# PCB_Schematic_Linefollower.net
KiCad netlist of a schematic drawn in EasyEDA
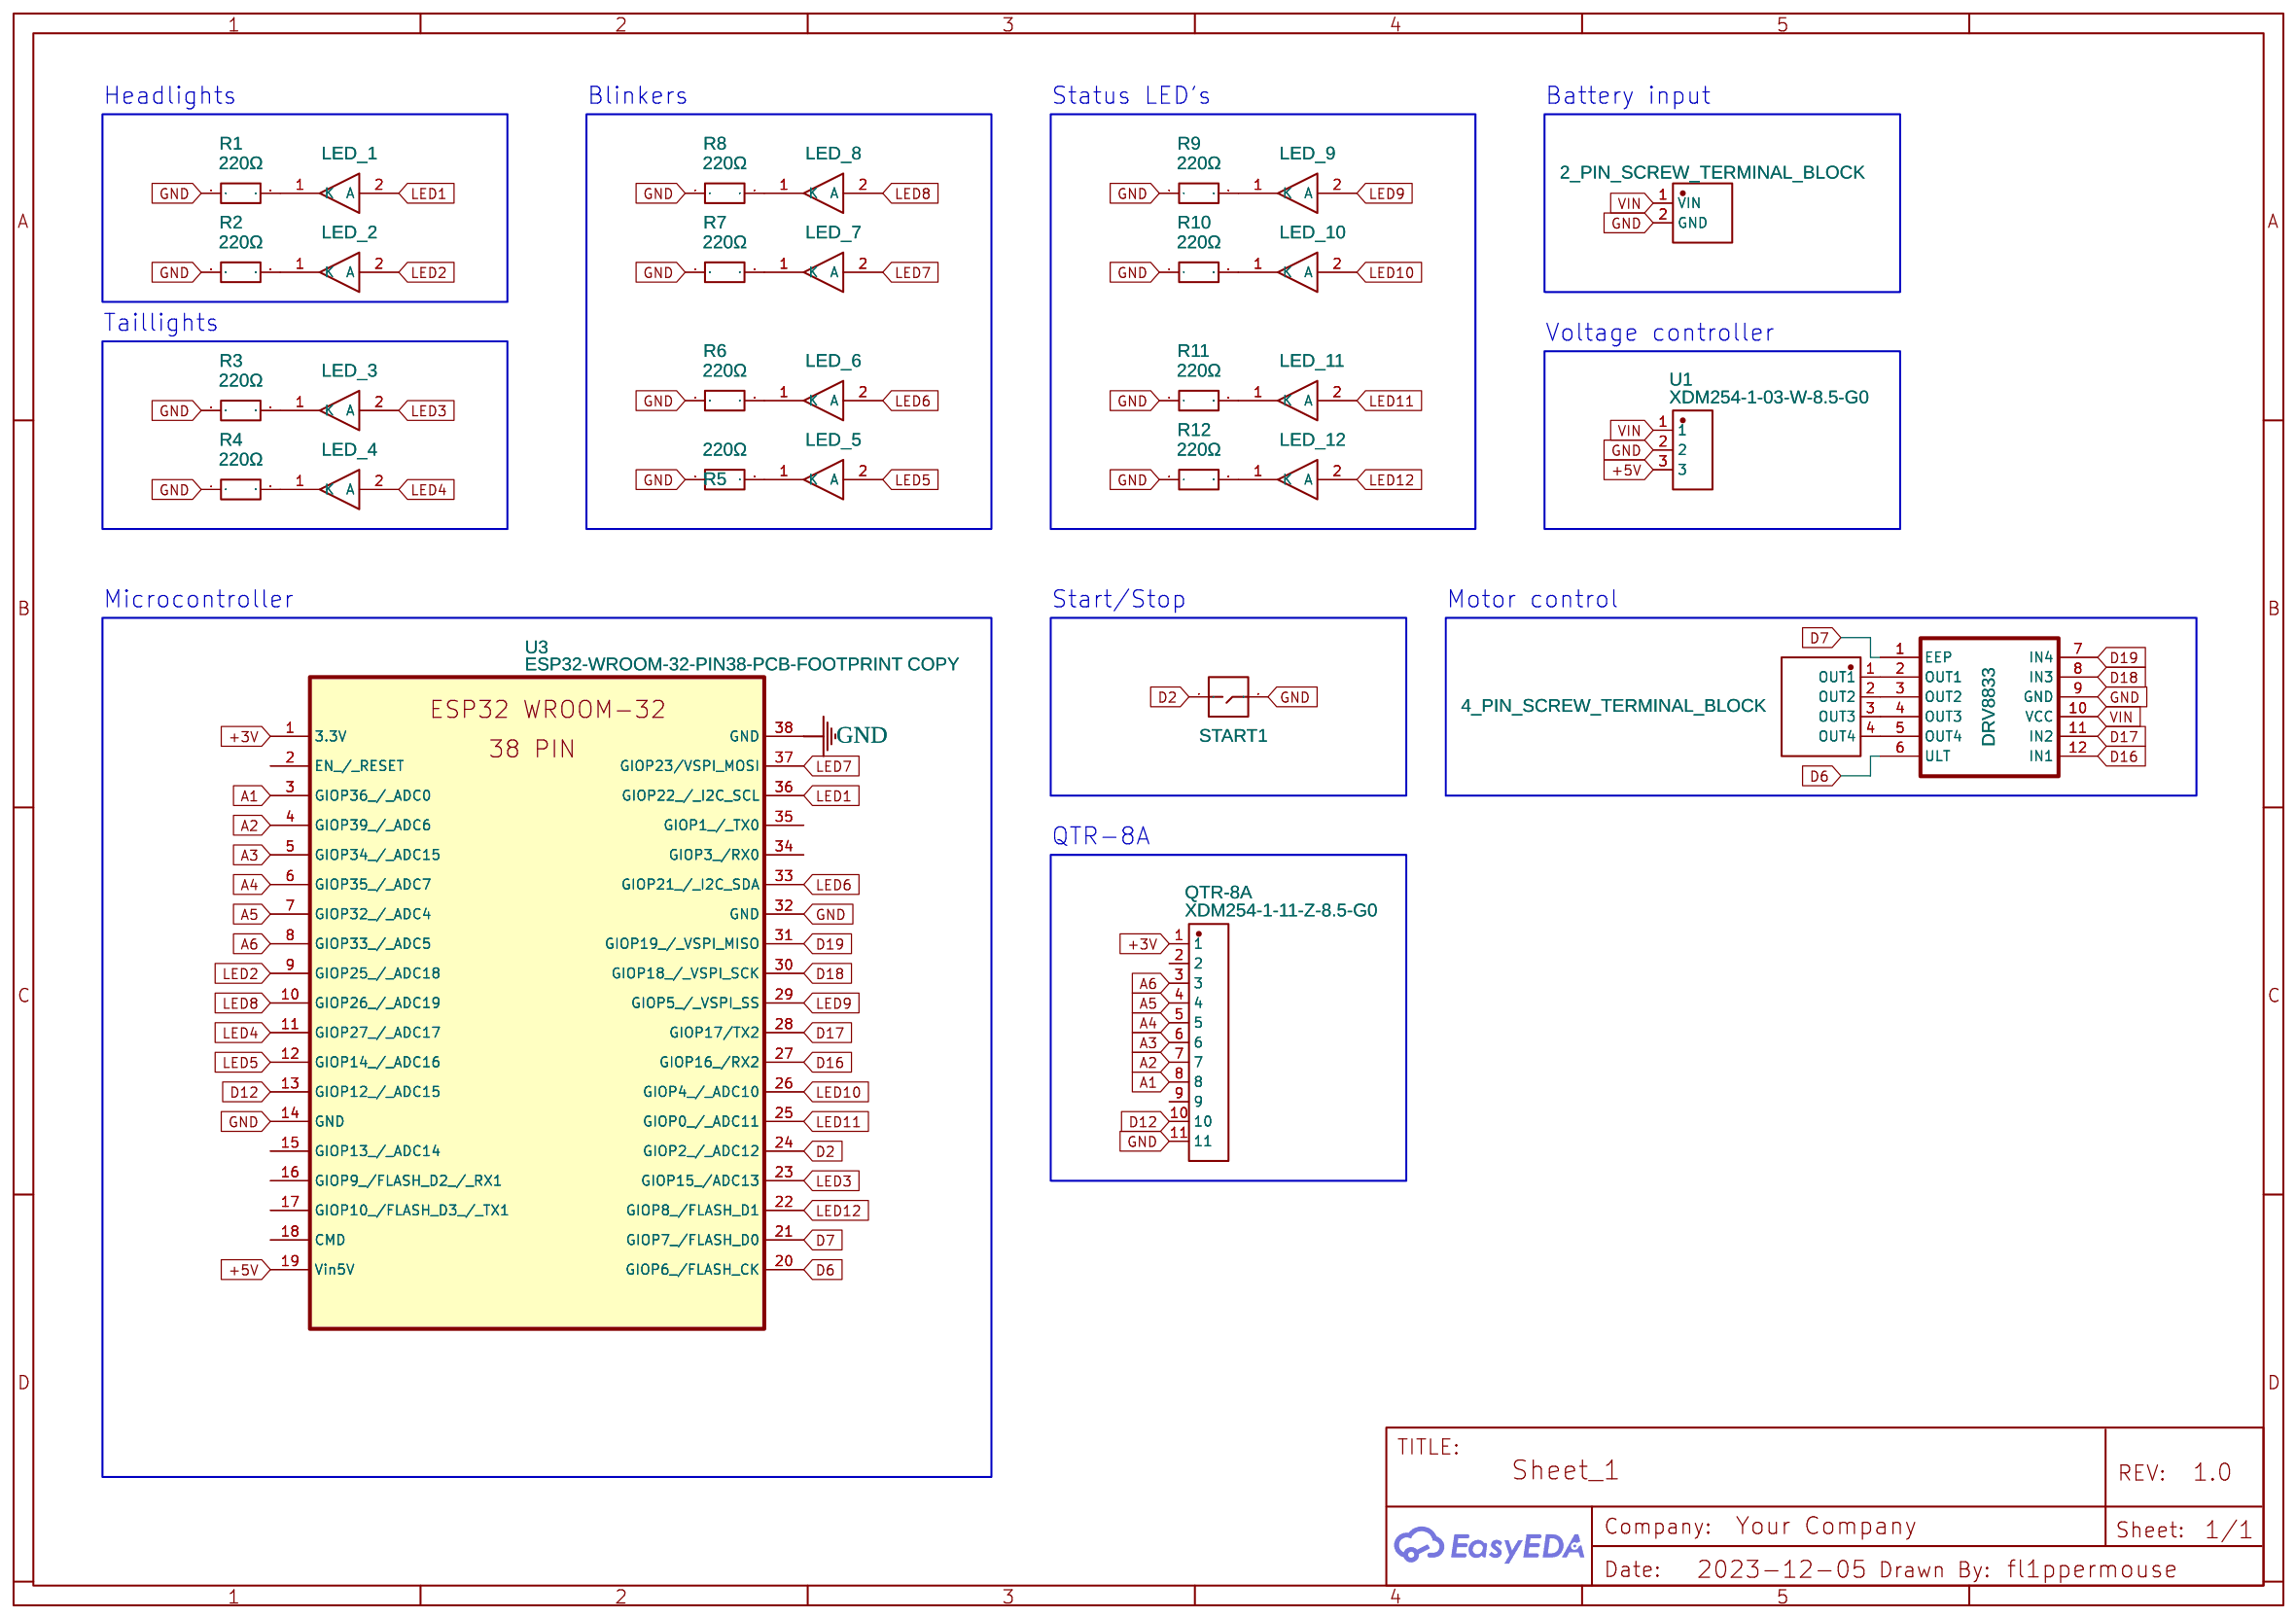
[diagram p0: schematic sheet]

(export (version "E")
  (design (tool "Eeschema 10.0.6"))
  (components
    (comp (ref "2_PIN_SCREW_TERMINAL_BLOCK")
      (value "2 Pin Screw Terminal Block Connector 2.54 mm")
      (libsource (lib "") (part "2 PIN SCREW TERMINAL BLOCK CONNECTOR 2.54 MM"))
    )
    (comp (ref "4_PIN_SCREW_TERMINAL_BLOCK")
      (value "4 PIN SCREW TERMINAL BLOCK CONNECTOR 2.54 MM")
      (libsource (lib "") (part "4 PIN SCREW TERMINAL BLOCK CONNECTOR 2.54 MM"))
    )
    (comp (ref "DRV8833") (value "DRV8833") (libsource (lib "") (part "DRV8833 12PIN")))
    (comp (ref "LED_1") (value "led 5 mm") (libsource (lib "") (part "led 5 mm")))
    (comp (ref "LED_2") (value "led 5 mm") (libsource (lib "") (part "led 5 mm")))
    (comp (ref "LED_3") (value "led 5 mm") (libsource (lib "") (part "led 5 mm")))
    (comp (ref "LED_4") (value "led 5 mm") (libsource (lib "") (part "led 5 mm")))
    (comp (ref "LED_5") (value "led 5 mm") (libsource (lib "") (part "led 5 mm")))
    (comp (ref "LED_6") (value "led 5 mm") (libsource (lib "") (part "led 5 mm")))
    (comp (ref "LED_7") (value "led 5 mm") (libsource (lib "") (part "led 5 mm")))
    (comp (ref "LED_8") (value "led 5 mm") (libsource (lib "") (part "led 5 mm")))
    (comp (ref "LED_9") (value "led 5 mm") (libsource (lib "") (part "led 5 mm")))
    (comp (ref "LED_10") (value "led 5 mm") (libsource (lib "") (part "led 5 mm")))
    (comp (ref "LED_11") (value "led 5 mm") (libsource (lib "") (part "led 5 mm")))
    (comp (ref "LED_12") (value "led 5 mm") (libsource (lib "") (part "led 5 mm")))
    (comp (ref "QTR-8A")
      (value "XDM254-1-11-Z-8.5-G0")
      (fields (field (name "Manufacturer") "XUNDA(讯答)"))
      (libsource (lib "") (part "XDM254-1-11-Z-8.5-G0"))
    )
    (comp (ref "R1")
      (value "220Ω")
      (libsource (lib "") (part "AXIAL RESISTOR 220 OHM - TH_BD2.3-L6.0-P10.00-D0.4"))
    )
    (comp (ref "R2")
      (value "220Ω")
      (libsource (lib "") (part "AXIAL RESISTOR 220 OHM - TH_BD2.3-L6.0-P10.00-D0.4"))
    )
    (comp (ref "R3")
      (value "220Ω")
      (libsource (lib "") (part "AXIAL RESISTOR 220 OHM - TH_BD2.3-L6.0-P10.00-D0.4"))
    )
    (comp (ref "R4")
      (value "220Ω")
      (libsource (lib "") (part "AXIAL RESISTOR 220 OHM - TH_BD2.3-L6.0-P10.00-D0.4"))
    )
    (comp (ref "R5")
      (value "220Ω")
      (libsource (lib "") (part "AXIAL RESISTOR 220 OHM - TH_BD2.3-L6.0-P10.00-D0.4"))
    )
    (comp (ref "R6")
      (value "220Ω")
      (libsource (lib "") (part "AXIAL RESISTOR 220 OHM - TH_BD2.3-L6.0-P10.00-D0.4"))
    )
    (comp (ref "R7")
      (value "220Ω")
      (libsource (lib "") (part "AXIAL RESISTOR 220 OHM - TH_BD2.3-L6.0-P10.00-D0.4"))
    )
    (comp (ref "R8")
      (value "220Ω")
      (libsource (lib "") (part "AXIAL RESISTOR 220 OHM - TH_BD2.3-L6.0-P10.00-D0.4"))
    )
    (comp (ref "R9")
      (value "220Ω")
      (libsource (lib "") (part "AXIAL RESISTOR 220 OHM - TH_BD2.3-L6.0-P10.00-D0.4"))
    )
    (comp (ref "R10")
      (value "220Ω")
      (libsource (lib "") (part "AXIAL RESISTOR 220 OHM - TH_BD2.3-L6.0-P10.00-D0.4"))
    )
    (comp (ref "R11")
      (value "220Ω")
      (libsource (lib "") (part "AXIAL RESISTOR 220 OHM - TH_BD2.3-L6.0-P10.00-D0.4"))
    )
    (comp (ref "R12")
      (value "220Ω")
      (libsource (lib "") (part "AXIAL RESISTOR 220 OHM - TH_BD2.3-L6.0-P10.00-D0.4"))
    )
    (comp (ref "START1") (value "start") (libsource (lib "") (part "Push Button")))
    (comp (ref "U1")
      (value "XDM254-1-03-W-8.5-G0")
      (fields (field (name "Manufacturer") "XUNDA(讯答)"))
      (libsource (lib "") (part "XDM254-1-03-W-8.5-G0"))
    )
    (comp (ref "U3")
      (value "ESP32-WROOM-32-PIN38-PCB-FOOTPRINT COPY")
      (fields
        (field (name "Manufacturer Part") "ESP32-WROOM-32")
        (field (name "Manufacturer") "Espressif Systems")
      )
      (libsource (lib "") (part "ESP32-WROOM-32-PIN38-PCB-FOOTPRINT COPY"))
    )
  )
  (nets
    (net (code "1") (name "+3V") (class "Default")
      (node (ref "QTR-8A") (pin "1") (pinfunction "1_1") (pintype "unspecified"))
      (node (ref "U3") (pin "1") (pinfunction "3.3V_1") (pintype "unspecified"))
    )
    (net (code "2") (name "+5V") (class "Default")
      (node (ref "U1") (pin "3") (pinfunction "3_3") (pintype "unspecified"))
      (node (ref "U3") (pin "19") (pinfunction "Vin5V_19") (pintype "unspecified"))
    )
    (net (code "3") (name "A1") (class "Default")
      (node (ref "QTR-8A") (pin "8") (pinfunction "8_8") (pintype "unspecified"))
      (node (ref "U3") (pin "3") (pinfunction "GIOP36_/_ADC0_3") (pintype "unspecified"))
    )
    (net (code "4") (name "A2") (class "Default")
      (node (ref "QTR-8A") (pin "7") (pinfunction "7_7") (pintype "unspecified"))
      (node (ref "U3") (pin "4") (pinfunction "GIOP39_/_ADC6_4") (pintype "unspecified"))
    )
    (net (code "5") (name "A3") (class "Default")
      (node (ref "QTR-8A") (pin "6") (pinfunction "6_6") (pintype "unspecified"))
      (node (ref "U3") (pin "5") (pinfunction "GIOP34_/_ADC15_5") (pintype "unspecified"))
    )
    (net (code "6") (name "A4") (class "Default")
      (node (ref "QTR-8A") (pin "5") (pinfunction "5_5") (pintype "unspecified"))
      (node (ref "U3") (pin "6") (pinfunction "GIOP35_/_ADC7_6") (pintype "unspecified"))
    )
    (net (code "7") (name "A5") (class "Default")
      (node (ref "QTR-8A") (pin "4") (pinfunction "4_4") (pintype "unspecified"))
      (node (ref "U3") (pin "7") (pinfunction "GIOP32_/_ADC4_7") (pintype "unspecified"))
    )
    (net (code "8") (name "A6") (class "Default")
      (node (ref "QTR-8A") (pin "3") (pinfunction "3_3") (pintype "unspecified"))
      (node (ref "U3") (pin "8") (pinfunction "GIOP33_/_ADC5_8") (pintype "unspecified"))
    )
    (net (code "9") (name "D2") (class "Default")
      (node (ref "START1") (pin "1") (pinfunction "1_1") (pintype "unspecified"))
      (node (ref "U3") (pin "24") (pinfunction "GIOP2_/_ADC12_24") (pintype "unspecified"))
    )
    (net (code "10") (name "D6") (class "Default")
      (node (ref "DRV8833") (pin "6") (pinfunction "ULT_6") (pintype "unspecified"))
      (node (ref "U3") (pin "20") (pinfunction "GIOP6_/FLASH_CK_20") (pintype "unspecified"))
    )
    (net (code "11") (name "D7") (class "Default")
      (node (ref "DRV8833") (pin "1") (pinfunction "EEP_1") (pintype "unspecified"))
      (node (ref "U3") (pin "21") (pinfunction "GIOP7_/FLASH_D0_21") (pintype "unspecified"))
    )
    (net (code "12") (name "D12") (class "Default")
      (node (ref "QTR-8A") (pin "10") (pinfunction "10_10") (pintype "unspecified"))
      (node (ref "U3") (pin "13") (pinfunction "GIOP12_/_ADC15_13") (pintype "unspecified"))
    )
    (net (code "13") (name "D16") (class "Default")
      (node (ref "DRV8833") (pin "12") (pinfunction "IN1_12") (pintype "unspecified"))
      (node (ref "U3") (pin "27") (pinfunction "GIOP16_/RX2_27") (pintype "unspecified"))
    )
    (net (code "14") (name "D17") (class "Default")
      (node (ref "DRV8833") (pin "11") (pinfunction "IN2_11") (pintype "unspecified"))
      (node (ref "U3") (pin "28") (pinfunction "GIOP17/TX2_28") (pintype "unspecified"))
    )
    (net (code "15") (name "D18") (class "Default")
      (node (ref "DRV8833") (pin "8") (pinfunction "IN3_8") (pintype "unspecified"))
      (node (ref "U3") (pin "30") (pinfunction "GIOP18_/_VSPI_SCK_30") (pintype "unspecified"))
    )
    (net (code "16") (name "D19") (class "Default")
      (node (ref "DRV8833") (pin "7") (pinfunction "IN4_7") (pintype "unspecified"))
      (node (ref "U3") (pin "31") (pinfunction "GIOP19_/_VSPI_MISO_31") (pintype "unspecified"))
    )
    (net (code "17") (name "GND") (class "Default")
      (node (ref "2_PIN_SCREW_TERMINAL_BLOCK") (pin "2") (pinfunction "GND_2") (pintype "unspecified"))
      (node (ref "DRV8833") (pin "9") (pinfunction "GND_9") (pintype "unspecified"))
      (node (ref "QTR-8A") (pin "11") (pinfunction "11_11") (pintype "unspecified"))
      (node (ref "R1") (pin "1") (pinfunction "1_1") (pintype "unspecified"))
      (node (ref "R10") (pin "1") (pinfunction "1_1") (pintype "unspecified"))
      (node (ref "R11") (pin "1") (pinfunction "1_1") (pintype "unspecified"))
      (node (ref "R12") (pin "1") (pinfunction "1_1") (pintype "unspecified"))
      (node (ref "R2") (pin "1") (pinfunction "1_1") (pintype "unspecified"))
      (node (ref "R3") (pin "1") (pinfunction "1_1") (pintype "unspecified"))
      (node (ref "R4") (pin "1") (pinfunction "1_1") (pintype "unspecified"))
      (node (ref "R5") (pin "1") (pinfunction "1_1") (pintype "unspecified"))
      (node (ref "R6") (pin "1") (pinfunction "1_1") (pintype "unspecified"))
      (node (ref "R7") (pin "1") (pinfunction "1_1") (pintype "unspecified"))
      (node (ref "R8") (pin "1") (pinfunction "1_1") (pintype "unspecified"))
      (node (ref "R9") (pin "1") (pinfunction "1_1") (pintype "unspecified"))
      (node (ref "START1") (pin "2") (pinfunction "2_2") (pintype "unspecified"))
      (node (ref "U1") (pin "2") (pinfunction "2_2") (pintype "unspecified"))
      (node (ref "U3") (pin "14") (pinfunction "GND_14") (pintype "unspecified"))
      (node (ref "U3") (pin "32") (pinfunction "GND_32") (pintype "unspecified"))
      (node (ref "U3") (pin "38") (pinfunction "GND_38") (pintype "unspecified"))
    )
    (net (code "18") (name "LED1") (class "Default")
      (node (ref "LED_1") (pin "2") (pinfunction "A_2") (pintype "unspecified"))
      (node (ref "U3") (pin "36") (pinfunction "GIOP22_/_I2C_SCL_36") (pintype "unspecified"))
    )
    (net (code "19") (name "LED2") (class "Default")
      (node (ref "LED_2") (pin "2") (pinfunction "A_2") (pintype "unspecified"))
      (node (ref "U3") (pin "9") (pinfunction "GIOP25_/_ADC18_9") (pintype "unspecified"))
    )
    (net (code "20") (name "LED3") (class "Default")
      (node (ref "LED_3") (pin "2") (pinfunction "A_2") (pintype "unspecified"))
      (node (ref "U3") (pin "23") (pinfunction "GIOP15_/ADC13_23") (pintype "unspecified"))
    )
    (net (code "21") (name "LED4") (class "Default")
      (node (ref "LED_4") (pin "2") (pinfunction "A_2") (pintype "unspecified"))
      (node (ref "U3") (pin "11") (pinfunction "GIOP27_/_ADC17_11") (pintype "unspecified"))
    )
    (net (code "22") (name "LED5") (class "Default")
      (node (ref "LED_5") (pin "2") (pinfunction "A_2") (pintype "unspecified"))
      (node (ref "U3") (pin "12") (pinfunction "GIOP14_/_ADC16_12") (pintype "unspecified"))
    )
    (net (code "23") (name "LED6") (class "Default")
      (node (ref "LED_6") (pin "2") (pinfunction "A_2") (pintype "unspecified"))
      (node (ref "U3") (pin "33") (pinfunction "GIOP21_/_I2C_SDA_33") (pintype "unspecified"))
    )
    (net (code "24") (name "LED7") (class "Default")
      (node (ref "LED_7") (pin "2") (pinfunction "A_2") (pintype "unspecified"))
      (node (ref "U3") (pin "37") (pinfunction "GIOP23/VSPI_MOSI_37") (pintype "unspecified"))
    )
    (net (code "25") (name "LED8") (class "Default")
      (node (ref "LED_8") (pin "2") (pinfunction "A_2") (pintype "unspecified"))
      (node (ref "U3") (pin "10") (pinfunction "GIOP26_/_ADC19_10") (pintype "unspecified"))
    )
    (net (code "26") (name "LED9") (class "Default")
      (node (ref "LED_9") (pin "2") (pinfunction "A_2") (pintype "unspecified"))
      (node (ref "U3") (pin "29") (pinfunction "GIOP5_/_VSPI_SS_29") (pintype "unspecified"))
    )
    (net (code "27") (name "LED10") (class "Default")
      (node (ref "LED_10") (pin "2") (pinfunction "A_2") (pintype "unspecified"))
      (node (ref "U3") (pin "26") (pinfunction "GIOP4_/_ADC10_26") (pintype "unspecified"))
    )
    (net (code "28") (name "LED11") (class "Default")
      (node (ref "LED_11") (pin "2") (pinfunction "A_2") (pintype "unspecified"))
      (node (ref "U3") (pin "25") (pinfunction "GIOP0_/_ADC11_25") (pintype "unspecified"))
    )
    (net (code "29") (name "LED12") (class "Default")
      (node (ref "LED_12") (pin "2") (pinfunction "A_2") (pintype "unspecified"))
      (node (ref "U3") (pin "22") (pinfunction "GIOP8_/FLASH_D1_22") (pintype "unspecified"))
    )
    (net (code "30") (name "Net-(4_PIN_SCREW_TERMINAL_BLOCK-OUT1)") (class "Default")
      (node (ref "4_PIN_SCREW_TERMINAL_BLOCK") (pin "1") (pinfunction "OUT1_1") (pintype "unspecified"))
      (node (ref "DRV8833") (pin "2") (pinfunction "OUT1_2") (pintype "unspecified"))
    )
    (net (code "31") (name "Net-(4_PIN_SCREW_TERMINAL_BLOCK-OUT2)") (class "Default")
      (node (ref "4_PIN_SCREW_TERMINAL_BLOCK") (pin "2") (pinfunction "OUT2_2") (pintype "unspecified"))
      (node (ref "DRV8833") (pin "3") (pinfunction "OUT2_3") (pintype "unspecified"))
    )
    (net (code "32") (name "Net-(4_PIN_SCREW_TERMINAL_BLOCK-OUT3)") (class "Default")
      (node (ref "4_PIN_SCREW_TERMINAL_BLOCK") (pin "3") (pinfunction "OUT3_3") (pintype "unspecified"))
      (node (ref "DRV8833") (pin "4") (pinfunction "OUT3_4") (pintype "unspecified"))
    )
    (net (code "33") (name "Net-(4_PIN_SCREW_TERMINAL_BLOCK-OUT4)") (class "Default")
      (node (ref "4_PIN_SCREW_TERMINAL_BLOCK") (pin "4") (pinfunction "OUT4_4") (pintype "unspecified"))
      (node (ref "DRV8833") (pin "5") (pinfunction "OUT4_5") (pintype "unspecified"))
    )
    (net (code "34") (name "Net-(LED_1-K)") (class "Default")
      (node (ref "LED_1") (pin "1") (pinfunction "K_1") (pintype "unspecified"))
      (node (ref "R1") (pin "2") (pinfunction "2_2") (pintype "unspecified"))
    )
    (net (code "35") (name "Net-(LED_2-K)") (class "Default")
      (node (ref "LED_2") (pin "1") (pinfunction "K_1") (pintype "unspecified"))
      (node (ref "R2") (pin "2") (pinfunction "2_2") (pintype "unspecified"))
    )
    (net (code "36") (name "Net-(LED_3-K)") (class "Default")
      (node (ref "LED_3") (pin "1") (pinfunction "K_1") (pintype "unspecified"))
      (node (ref "R3") (pin "2") (pinfunction "2_2") (pintype "unspecified"))
    )
    (net (code "37") (name "Net-(LED_4-K)") (class "Default")
      (node (ref "LED_4") (pin "1") (pinfunction "K_1") (pintype "unspecified"))
      (node (ref "R4") (pin "2") (pinfunction "2_2") (pintype "unspecified"))
    )
    (net (code "38") (name "Net-(LED_5-K)") (class "Default")
      (node (ref "LED_5") (pin "1") (pinfunction "K_1") (pintype "unspecified"))
      (node (ref "R5") (pin "2") (pinfunction "2_2") (pintype "unspecified"))
    )
    (net (code "39") (name "Net-(LED_6-K)") (class "Default")
      (node (ref "LED_6") (pin "1") (pinfunction "K_1") (pintype "unspecified"))
      (node (ref "R6") (pin "2") (pinfunction "2_2") (pintype "unspecified"))
    )
    (net (code "40") (name "Net-(LED_7-K)") (class "Default")
      (node (ref "LED_7") (pin "1") (pinfunction "K_1") (pintype "unspecified"))
      (node (ref "R7") (pin "2") (pinfunction "2_2") (pintype "unspecified"))
    )
    (net (code "41") (name "Net-(LED_8-K)") (class "Default")
      (node (ref "LED_8") (pin "1") (pinfunction "K_1") (pintype "unspecified"))
      (node (ref "R8") (pin "2") (pinfunction "2_2") (pintype "unspecified"))
    )
    (net (code "42") (name "Net-(LED_9-K)") (class "Default")
      (node (ref "LED_9") (pin "1") (pinfunction "K_1") (pintype "unspecified"))
      (node (ref "R9") (pin "2") (pinfunction "2_2") (pintype "unspecified"))
    )
    (net (code "43") (name "Net-(LED_10-K)") (class "Default")
      (node (ref "LED_10") (pin "1") (pinfunction "K_1") (pintype "unspecified"))
      (node (ref "R10") (pin "2") (pinfunction "2_2") (pintype "unspecified"))
    )
    (net (code "44") (name "Net-(LED_11-K)") (class "Default")
      (node (ref "LED_11") (pin "1") (pinfunction "K_1") (pintype "unspecified"))
      (node (ref "R11") (pin "2") (pinfunction "2_2") (pintype "unspecified"))
    )
    (net (code "45") (name "Net-(LED_12-K)") (class "Default")
      (node (ref "LED_12") (pin "1") (pinfunction "K_1") (pintype "unspecified"))
      (node (ref "R12") (pin "2") (pinfunction "2_2") (pintype "unspecified"))
    )
    (net (code "46") (name "VIN") (class "Default")
      (node (ref "2_PIN_SCREW_TERMINAL_BLOCK") (pin "1") (pinfunction "VIN_1") (pintype "unspecified"))
      (node (ref "DRV8833") (pin "10") (pinfunction "VCC_10") (pintype "unspecified"))
      (node (ref "U1") (pin "1") (pinfunction "1_1") (pintype "unspecified"))
    )
    (net (code "47") (name "unconnected-(QTR-8A-Pad2)") (class "Default")
      (node (ref "QTR-8A") (pin "2") (pinfunction "2_2") (pintype "unspecified"))
    )
    (net (code "48") (name "unconnected-(QTR-8A-Pad9)") (class "Default")
      (node (ref "QTR-8A") (pin "9") (pinfunction "9_9") (pintype "unspecified"))
    )
    (net (code "49") (name "unconnected-(U3-CMD-Pad18)") (class "Default")
      (node (ref "U3") (pin "18") (pinfunction "CMD_18") (pintype "unspecified"))
    )
    (net (code "50") (name "unconnected-(U3-EN_{slash}_RESET-Pad2)") (class "Default")
      (node (ref "U3") (pin "2") (pinfunction "EN_/_RESET_2") (pintype "unspecified"))
    )
    (net (code "51") (name "unconnected-(U3-GIOP1_{slash}_TX0-Pad35)") (class "Default")
      (node (ref "U3") (pin "35") (pinfunction "GIOP1_/_TX0_35") (pintype "unspecified"))
    )
    (net (code "52") (name "unconnected-(U3-GIOP3_{slash}RX0-Pad34)") (class "Default")
      (node (ref "U3") (pin "34") (pinfunction "GIOP3_/RX0_34") (pintype "unspecified"))
    )
    (net (code "53") (name "unconnected-(U3-GIOP9_{slash}FLASH_D2_{slash}_RX1-Pad16)") (class "Default")
      (node (ref "U3") (pin "16") (pinfunction "GIOP9_/FLASH_D2_/_RX1_16") (pintype "unspecified"))
    )
    (net (code "54") (name "unconnected-(U3-GIOP10_{slash}FLASH_D3_{slash}_TX1-Pad17)") (class "Default")
      (node (ref "U3") (pin "17") (pinfunction "GIOP10_/FLASH_D3_/_TX1_17") (pintype "unspecified"))
    )
    (net (code "55") (name "unconnected-(U3-GIOP13_{slash}_ADC14-Pad15)") (class "Default")
      (node (ref "U3") (pin "15") (pinfunction "GIOP13_/_ADC14_15") (pintype "unspecified"))
    )
  )
)
